# Driver2.net
KiCad netlist of a schematic drawn in Altium Designer
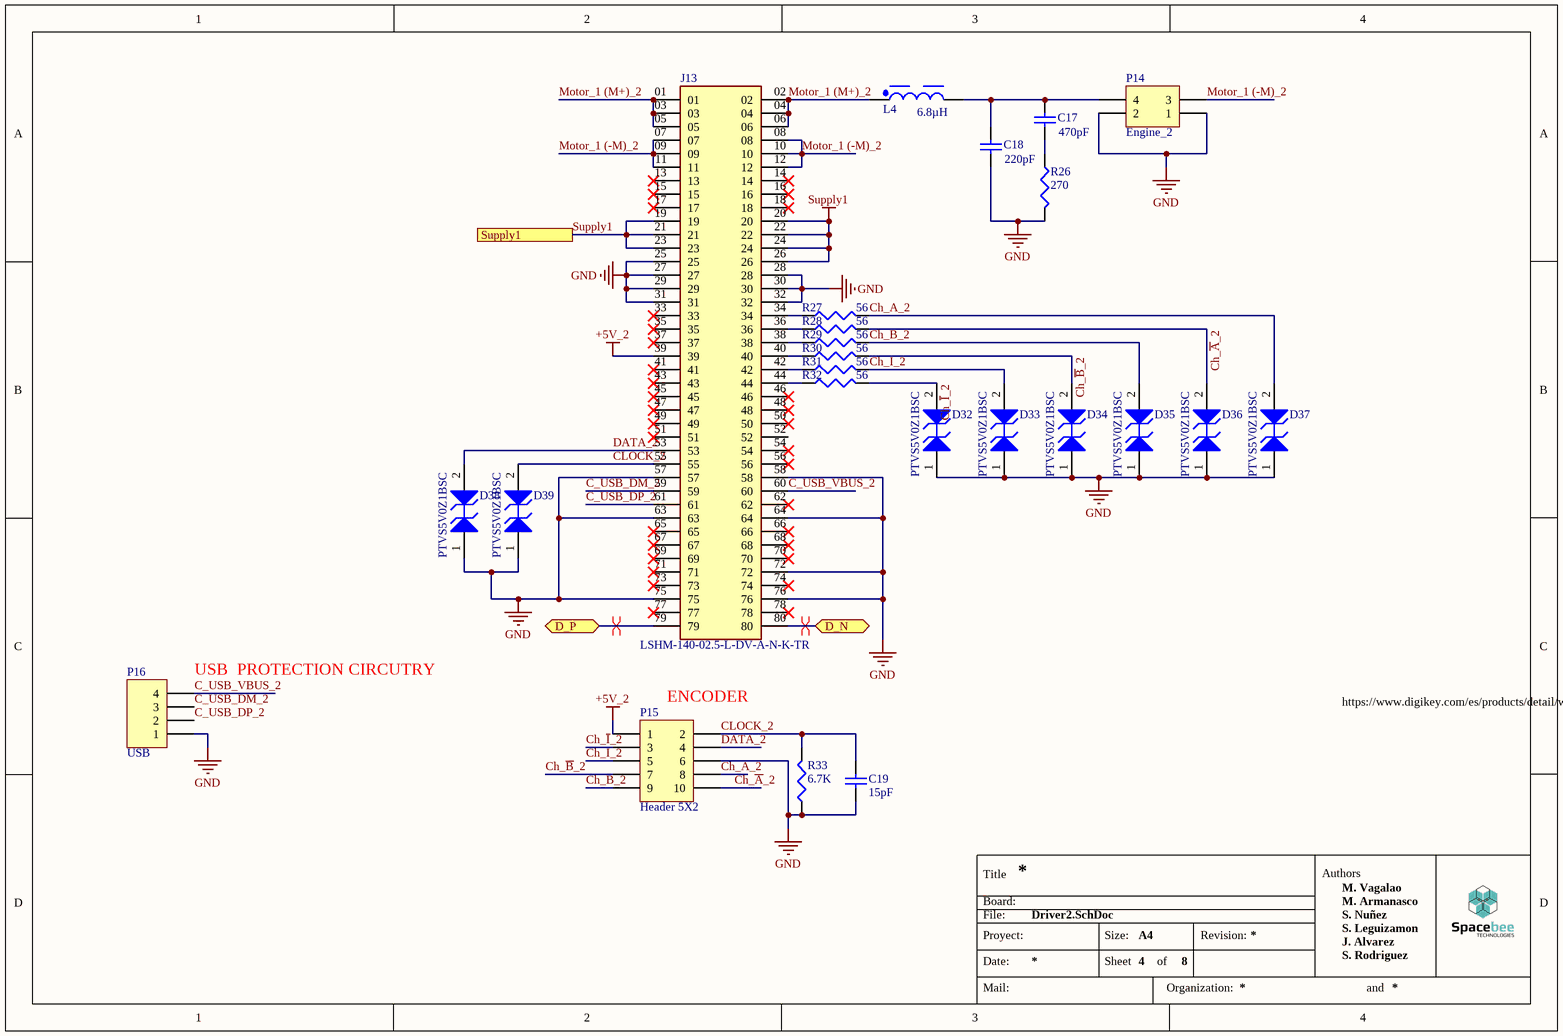
[diagram p0: Driver2.SchDoc]

(export (version "E")
  (design (tool "Eeschema 10.0.6"))
  (components
    (comp (ref "C17")
      (value "470pF")
      (footprint "1608[0603]")
      (description "Capacitor (Semiconductor SIM Model)")
      (fields (field (name "Comment") "Cap Semi") (field (name "PUBLISHER") "Altium Limited"))
      (libsource (lib "Miscellaneous Devices") (part "Cap Semi"))
    )
    (comp (ref "C18")
      (value "220pF")
      (footprint "1608[0603]")
      (description "Capacitor (Semiconductor SIM Model)")
      (fields (field (name "Comment") "Cap Semi") (field (name "PUBLISHER") "Altium Limited"))
      (libsource (lib "Miscellaneous Devices") (part "Cap Semi"))
    )
    (comp (ref "C19")
      (value "15pF")
      (footprint "6-0805_L")
      (description "Capacitor (Semiconductor SIM Model)")
      (fields (field (name "Comment") "Cap Semi") (field (name "PUBLISHER") "Altium Limited"))
      (libsource (lib "SpaceBee") (part "Cap 0805"))
    )
    (comp (ref "D32")
      (value "PTVS5V0Z1BSC")
      (footprint "SOD993B")
      (fields (field (name "MANUFACTURER") "On Semiconductor") (field (name "PARTNUMBER") "1SMB16CAT3"))
      (libsource (lib "DriverLib") (part "PTVS5V0Z1BSC"))
    )
    (comp (ref "D33")
      (value "PTVS5V0Z1BSC")
      (footprint "SOD993B")
      (fields (field (name "MANUFACTURER") "On Semiconductor") (field (name "PARTNUMBER") "1SMB16CAT3"))
      (libsource (lib "DriverLib") (part "PTVS5V0Z1BSC"))
    )
    (comp (ref "D34")
      (value "PTVS5V0Z1BSC")
      (footprint "SOD993B")
      (fields (field (name "MANUFACTURER") "On Semiconductor") (field (name "PARTNUMBER") "1SMB16CAT3"))
      (libsource (lib "DriverLib") (part "PTVS5V0Z1BSC"))
    )
    (comp (ref "D35")
      (value "PTVS5V0Z1BSC")
      (footprint "SOD993B")
      (fields (field (name "MANUFACTURER") "On Semiconductor") (field (name "PARTNUMBER") "1SMB16CAT3"))
      (libsource (lib "DriverLib") (part "PTVS5V0Z1BSC"))
    )
    (comp (ref "D36")
      (value "PTVS5V0Z1BSC")
      (footprint "SOD993B")
      (fields (field (name "MANUFACTURER") "On Semiconductor") (field (name "PARTNUMBER") "1SMB16CAT3"))
      (libsource (lib "DriverLib") (part "PTVS5V0Z1BSC"))
    )
    (comp (ref "D37")
      (value "PTVS5V0Z1BSC")
      (footprint "SOD993B")
      (fields (field (name "MANUFACTURER") "On Semiconductor") (field (name "PARTNUMBER") "1SMB16CAT3"))
      (libsource (lib "DriverLib") (part "PTVS5V0Z1BSC"))
    )
    (comp (ref "D38")
      (value "PTVS5V0Z1BSC")
      (footprint "SOD993B")
      (fields (field (name "MANUFACTURER") "On Semiconductor") (field (name "PARTNUMBER") "1SMB16CAT3"))
      (libsource (lib "DriverLib") (part "PTVS5V0Z1BSC"))
    )
    (comp (ref "D39")
      (value "PTVS5V0Z1BSC")
      (footprint "SOD993B")
      (fields (field (name "MANUFACTURER") "On Semiconductor") (field (name "PARTNUMBER") "1SMB16CAT3"))
      (libsource (lib "DriverLib") (part "PTVS5V0Z1BSC"))
    )
    (comp (ref "J13")
      (value "LSHM-140-02.5-L-DV-A-N-K-TR")
      (footprint "SAMTEC_LSHM-140-02.5-L-DV-A-N-K-TR")
      (description "LSHM - Samtec 0.50mm Razor Beam High-Speed Hermaphroditic Terminal / Socket Strip.")
      (libsource (lib "DriverLib") (part "LSHM-140-02.5-L-DV-A-N-K-TR"))
    )
    (comp (ref "L4")
      (value "6.8µH")
      (footprint "WE-XHMA_6060")
      (description "WE-XHMA SMD Power Inductor, size 1090, 6.8µH, 10.5A, 7.16mΩ")
      (fields
        (field (name "MANUFACTURER PART NUMBER") "78439369068")
        (field (name "MANUFACTURER") "Wurth Elektronik")
      )
      (libsource (lib "DriverLib") (part "78439369068"))
    )
    (comp (ref "P14")
      (value "Engine_2")
      (footprint "MOLEX_1724480004")
      (description "Header, 2-Pin, Dual row")
      (fields (field (name "PUBLISHER") "Altium Limited"))
      (libsource (lib "SpaceBee") (part "Header 2X2"))
    )
    (comp (ref "P15")
      (value "Header 5X2")
      (footprint "CONN_HIF3FC-14PA-2.54DS(71)_HIR")
      (description "Header, 5-Pin, Dual row")
      (fields (field (name "PUBLISHER") "Altium Limited"))
      (libsource (lib "DriverLib") (part "Header 5X2"))
    )
    (comp (ref "P16")
      (value "USB")
      (footprint "Header 4 SMD")
      (description "Header, 4-Pin")
      (fields (field (name "PUBLISHER") "Altium Limited"))
      (libsource (lib "SpaceBee") (part "Header 4 SMD"))
    )
    (comp (ref "R26")
      (value "270")
      (footprint "J1-0603")
      (description "Resistor")
      (fields (field (name "Comment") "Res3") (field (name "PUBLISHER") "Altium Limited"))
      (libsource (lib "Miscellaneous Devices") (part "Res3"))
    )
    (comp (ref "R27")
      (value "56")
      (footprint "J1-0603")
      (description "Resistor")
      (fields (field (name "Comment") "Res3") (field (name "PUBLISHER") "Altium Limited"))
      (libsource (lib "Miscellaneous Devices") (part "Res3"))
    )
    (comp (ref "R28")
      (value "56")
      (footprint "J1-0603")
      (description "Resistor")
      (fields (field (name "Comment") "Res3") (field (name "PUBLISHER") "Altium Limited"))
      (libsource (lib "Miscellaneous Devices") (part "Res3"))
    )
    (comp (ref "R29")
      (value "56")
      (footprint "J1-0603")
      (description "Resistor")
      (fields (field (name "Comment") "Res3") (field (name "PUBLISHER") "Altium Limited"))
      (libsource (lib "Miscellaneous Devices") (part "Res3"))
    )
    (comp (ref "R30")
      (value "56")
      (footprint "J1-0603")
      (description "Resistor")
      (fields (field (name "Comment") "Res3") (field (name "PUBLISHER") "Altium Limited"))
      (libsource (lib "Miscellaneous Devices") (part "Res3"))
    )
    (comp (ref "R31")
      (value "56")
      (footprint "J1-0603")
      (description "Resistor")
      (fields (field (name "Comment") "Res3") (field (name "PUBLISHER") "Altium Limited"))
      (libsource (lib "Miscellaneous Devices") (part "Res3"))
    )
    (comp (ref "R32")
      (value "56")
      (footprint "J1-0603")
      (description "Resistor")
      (fields (field (name "Comment") "Res3") (field (name "PUBLISHER") "Altium Limited"))
      (libsource (lib "Miscellaneous Devices") (part "Res3"))
    )
    (comp (ref "R33")
      (value "6.7K")
      (footprint "J1-0603")
      (description "Resistor")
      (fields (field (name "Comment") "Res3") (field (name "PUBLISHER") "Altium Limited"))
      (libsource (lib "Miscellaneous Devices") (part "Res3"))
    )
  )
  (nets
    (net (code "1") (name "+5V_2") (class "Default")
      (node (ref "J13") (pin "39") (pinfunction "39_39") (pintype "passive"))
      (node (ref "P15") (pin "1") (pinfunction "1_1") (pintype "passive"))
    )
    (net (code "2") (name "/CLOCK_2") (class "Default")
      (node (ref "C19") (pin "2") (pinfunction "2_2") (pintype "passive"))
      (node (ref "D39") (pin "2") (pinfunction "A2_2") (pintype "passive"))
      (node (ref "J13") (pin "55") (pinfunction "55_55") (pintype "passive"))
      (node (ref "P15") (pin "2") (pinfunction "2_2") (pintype "passive"))
      (node (ref "R33") (pin "2") (pinfunction "2_2") (pintype "passive"))
    )
    (net (code "3") (name "/C_USB_DM_2") (class "Default")
      (node (ref "J13") (pin "59") (pinfunction "59_59") (pintype "passive"))
      (node (ref "P16") (pin "3") (pinfunction "3_3") (pintype "passive"))
    )
    (net (code "4") (name "/C_USB_DP_2") (class "Default")
      (node (ref "J13") (pin "61") (pinfunction "61_61") (pintype "passive"))
      (node (ref "P16") (pin "2") (pinfunction "2_2") (pintype "passive"))
    )
    (net (code "5") (name "/C_USB_VBUS_2") (class "Default")
      (node (ref "J13") (pin "60") (pinfunction "60_60") (pintype "passive"))
      (node (ref "P16") (pin "4") (pinfunction "4_4") (pintype "passive"))
    )
    (net (code "6") (name "/Ch_A_2") (class "Default")
      (node (ref "D37") (pin "2") (pinfunction "A2_2") (pintype "passive"))
      (node (ref "P15") (pin "8") (pinfunction "8_8") (pintype "passive"))
      (node (ref "R27") (pin "2") (pinfunction "2_2") (pintype "passive"))
    )
    (net (code "7") (name "/Ch_B_2") (class "Default")
      (node (ref "D35") (pin "2") (pinfunction "A2_2") (pintype "passive"))
      (node (ref "P15") (pin "9") (pinfunction "9_9") (pintype "passive"))
      (node (ref "R29") (pin "2") (pinfunction "2_2") (pintype "passive"))
    )
    (net (code "8") (name "/Ch_I_2") (class "Default")
      (node (ref "D33") (pin "2") (pinfunction "A2_2") (pintype "passive"))
      (node (ref "P15") (pin "5") (pinfunction "5_5") (pintype "passive"))
      (node (ref "R31") (pin "2") (pinfunction "2_2") (pintype "passive"))
    )
    (net (code "9") (name "/Ch_~{A}_2") (class "Default")
      (node (ref "D36") (pin "2") (pinfunction "A2_2") (pintype "passive"))
      (node (ref "P15") (pin "10") (pinfunction "10_10") (pintype "passive"))
      (node (ref "R28") (pin "2") (pinfunction "2_2") (pintype "passive"))
    )
    (net (code "10") (name "/Ch_~{B}_2") (class "Default")
      (node (ref "D34") (pin "2") (pinfunction "A2_2") (pintype "passive"))
      (node (ref "P15") (pin "7") (pinfunction "7_7") (pintype "passive"))
      (node (ref "R30") (pin "2") (pinfunction "2_2") (pintype "passive"))
    )
    (net (code "11") (name "/Ch_~{I}_2") (class "Default")
      (node (ref "D32") (pin "2") (pinfunction "A2_2") (pintype "passive"))
      (node (ref "P15") (pin "3") (pinfunction "3_3") (pintype "passive"))
      (node (ref "R32") (pin "2") (pinfunction "2_2") (pintype "passive"))
    )
    (net (code "12") (name "/DATA_2") (class "Default")
      (node (ref "D38") (pin "2") (pinfunction "A2_2") (pintype "passive"))
      (node (ref "J13") (pin "53") (pinfunction "53_53") (pintype "passive"))
      (node (ref "P15") (pin "4") (pinfunction "4_4") (pintype "passive"))
    )
    (net (code "13") (name "/D_N") (class "Default")
      (node (ref "J13") (pin "80") (pinfunction "80_80") (pintype "passive"))
    )
    (net (code "14") (name "/D_P") (class "Default")
      (node (ref "J13") (pin "79") (pinfunction "79_79") (pintype "passive"))
    )
    (net (code "15") (name "/Motor_1 (-M)_2") (class "Default")
      (node (ref "J13") (pin "07") (pinfunction "07_07") (pintype "passive"))
      (node (ref "J13") (pin "08") (pinfunction "08_08") (pintype "passive"))
      (node (ref "J13") (pin "09") (pinfunction "09_09") (pintype "passive"))
      (node (ref "J13") (pin "10") (pinfunction "10_10") (pintype "passive"))
      (node (ref "J13") (pin "11") (pinfunction "11_11") (pintype "passive"))
      (node (ref "J13") (pin "12") (pinfunction "12_12") (pintype "passive"))
      (node (ref "P14") (pin "3") (pinfunction "3_3") (pintype "passive"))
    )
    (net (code "16") (name "/Motor_1 (M+)_2") (class "Default")
      (node (ref "J13") (pin "01") (pinfunction "01_01") (pintype "passive"))
      (node (ref "J13") (pin "02") (pinfunction "02_02") (pintype "passive"))
      (node (ref "J13") (pin "03") (pinfunction "03_03") (pintype "passive"))
      (node (ref "J13") (pin "04") (pinfunction "04_04") (pintype "passive"))
      (node (ref "J13") (pin "05") (pinfunction "05_05") (pintype "passive"))
      (node (ref "J13") (pin "06") (pinfunction "06_06") (pintype "passive"))
      (node (ref "L4") (pin "1") (pinfunction "1_1") (pintype "passive"))
    )
    (net (code "17") (name "GND") (class "Default")
      (node (ref "C18") (pin "2") (pinfunction "2_2") (pintype "passive"))
      (node (ref "C19") (pin "1") (pinfunction "1_1") (pintype "passive"))
      (node (ref "D32") (pin "1") (pinfunction "A1_1") (pintype "passive"))
      (node (ref "D33") (pin "1") (pinfunction "A1_1") (pintype "passive"))
      (node (ref "D34") (pin "1") (pinfunction "A1_1") (pintype "passive"))
      (node (ref "D35") (pin "1") (pinfunction "A1_1") (pintype "passive"))
      (node (ref "D36") (pin "1") (pinfunction "A1_1") (pintype "passive"))
      (node (ref "D37") (pin "1") (pinfunction "A1_1") (pintype "passive"))
      (node (ref "D38") (pin "1") (pinfunction "A1_1") (pintype "passive"))
      (node (ref "D39") (pin "1") (pinfunction "A1_1") (pintype "passive"))
      (node (ref "J13") (pin "25") (pinfunction "25_25") (pintype "passive"))
      (node (ref "J13") (pin "27") (pinfunction "27_27") (pintype "passive"))
      (node (ref "J13") (pin "28") (pinfunction "28_28") (pintype "passive"))
      (node (ref "J13") (pin "29") (pinfunction "29_29") (pintype "passive"))
      (node (ref "J13") (pin "30") (pinfunction "30_30") (pintype "passive"))
      (node (ref "J13") (pin "31") (pinfunction "31_31") (pintype "passive"))
      (node (ref "J13") (pin "32") (pinfunction "32_32") (pintype "passive"))
      (node (ref "J13") (pin "57") (pinfunction "57_57") (pintype "passive"))
      (node (ref "J13") (pin "58") (pinfunction "58_58") (pintype "passive"))
      (node (ref "J13") (pin "63") (pinfunction "63_63") (pintype "passive"))
      (node (ref "J13") (pin "64") (pinfunction "64_64") (pintype "passive"))
      (node (ref "J13") (pin "72") (pinfunction "72_72") (pintype "passive"))
      (node (ref "J13") (pin "75") (pinfunction "75_75") (pintype "passive"))
      (node (ref "J13") (pin "76") (pinfunction "76_76") (pintype "passive"))
      (node (ref "P14") (pin "1") (pinfunction "1_1") (pintype "passive"))
      (node (ref "P14") (pin "2") (pinfunction "2_2") (pintype "passive"))
      (node (ref "P15") (pin "6") (pinfunction "6_6") (pintype "passive"))
      (node (ref "P16") (pin "1") (pinfunction "1_1") (pintype "passive"))
      (node (ref "R26") (pin "2") (pinfunction "2_2") (pintype "passive"))
      (node (ref "R33") (pin "1") (pinfunction "1_1") (pintype "passive"))
    )
    (net (code "18") (name "Net-(C17-Pad1)") (class "Default")
      (node (ref "C17") (pin "1") (pinfunction "1_1") (pintype "passive"))
      (node (ref "C18") (pin "1") (pinfunction "1_1") (pintype "passive"))
      (node (ref "L4") (pin "2") (pinfunction "2_2") (pintype "passive"))
      (node (ref "P14") (pin "4") (pinfunction "4_4") (pintype "passive"))
    )
    (net (code "19") (name "Net-(C17-Pad2)") (class "Default")
      (node (ref "C17") (pin "2") (pinfunction "2_2") (pintype "passive"))
      (node (ref "R26") (pin "1") (pinfunction "1_1") (pintype "passive"))
    )
    (net (code "20") (name "Net-(J13-Pad34)") (class "Default")
      (node (ref "J13") (pin "34") (pinfunction "34_34") (pintype "passive"))
      (node (ref "R27") (pin "1") (pinfunction "1_1") (pintype "passive"))
    )
    (net (code "21") (name "Net-(J13-Pad36)") (class "Default")
      (node (ref "J13") (pin "36") (pinfunction "36_36") (pintype "passive"))
      (node (ref "R28") (pin "1") (pinfunction "1_1") (pintype "passive"))
    )
    (net (code "22") (name "Net-(J13-Pad38)") (class "Default")
      (node (ref "J13") (pin "38") (pinfunction "38_38") (pintype "passive"))
      (node (ref "R29") (pin "1") (pinfunction "1_1") (pintype "passive"))
    )
    (net (code "23") (name "Net-(J13-Pad40)") (class "Default")
      (node (ref "J13") (pin "40") (pinfunction "40_40") (pintype "passive"))
      (node (ref "R30") (pin "1") (pinfunction "1_1") (pintype "passive"))
    )
    (net (code "24") (name "Net-(J13-Pad42)") (class "Default")
      (node (ref "J13") (pin "42") (pinfunction "42_42") (pintype "passive"))
      (node (ref "R31") (pin "1") (pinfunction "1_1") (pintype "passive"))
    )
    (net (code "25") (name "Net-(J13-Pad44)") (class "Default")
      (node (ref "J13") (pin "44") (pinfunction "44_44") (pintype "passive"))
      (node (ref "R32") (pin "1") (pinfunction "1_1") (pintype "passive"))
    )
    (net (code "26") (name "Supply1") (class "Default")
      (node (ref "J13") (pin "19") (pinfunction "19_19") (pintype "passive"))
      (node (ref "J13") (pin "20") (pinfunction "20_20") (pintype "passive"))
      (node (ref "J13") (pin "21") (pinfunction "21_21") (pintype "passive"))
      (node (ref "J13") (pin "22") (pinfunction "22_22") (pintype "passive"))
      (node (ref "J13") (pin "23") (pinfunction "23_23") (pintype "passive"))
      (node (ref "J13") (pin "24") (pinfunction "24_24") (pintype "passive"))
      (node (ref "J13") (pin "26") (pinfunction "26_26") (pintype "passive"))
    )
    (net (code "27") (name "unconnected-(J13-Pad13)") (class "Default")
      (node (ref "J13") (pin "13") (pinfunction "13_13") (pintype "passive+no_connect"))
    )
    (net (code "28") (name "unconnected-(J13-Pad14)") (class "Default")
      (node (ref "J13") (pin "14") (pinfunction "14_14") (pintype "passive+no_connect"))
    )
    (net (code "29") (name "unconnected-(J13-Pad15)") (class "Default")
      (node (ref "J13") (pin "15") (pinfunction "15_15") (pintype "passive+no_connect"))
    )
    (net (code "30") (name "unconnected-(J13-Pad16)") (class "Default")
      (node (ref "J13") (pin "16") (pinfunction "16_16") (pintype "passive+no_connect"))
    )
    (net (code "31") (name "unconnected-(J13-Pad17)") (class "Default")
      (node (ref "J13") (pin "17") (pinfunction "17_17") (pintype "passive+no_connect"))
    )
    (net (code "32") (name "unconnected-(J13-Pad18)") (class "Default")
      (node (ref "J13") (pin "18") (pinfunction "18_18") (pintype "passive+no_connect"))
    )
    (net (code "33") (name "unconnected-(J13-Pad33)") (class "Default")
      (node (ref "J13") (pin "33") (pinfunction "33_33") (pintype "passive+no_connect"))
    )
    (net (code "34") (name "unconnected-(J13-Pad35)") (class "Default")
      (node (ref "J13") (pin "35") (pinfunction "35_35") (pintype "passive+no_connect"))
    )
    (net (code "35") (name "unconnected-(J13-Pad37)") (class "Default")
      (node (ref "J13") (pin "37") (pinfunction "37_37") (pintype "passive+no_connect"))
    )
    (net (code "36") (name "unconnected-(J13-Pad41)") (class "Default")
      (node (ref "J13") (pin "41") (pinfunction "41_41") (pintype "passive+no_connect"))
    )
    (net (code "37") (name "unconnected-(J13-Pad43)") (class "Default")
      (node (ref "J13") (pin "43") (pinfunction "43_43") (pintype "passive+no_connect"))
    )
    (net (code "38") (name "unconnected-(J13-Pad45)") (class "Default")
      (node (ref "J13") (pin "45") (pinfunction "45_45") (pintype "passive+no_connect"))
    )
    (net (code "39") (name "unconnected-(J13-Pad46)") (class "Default")
      (node (ref "J13") (pin "46") (pinfunction "46_46") (pintype "passive+no_connect"))
    )
    (net (code "40") (name "unconnected-(J13-Pad47)") (class "Default")
      (node (ref "J13") (pin "47") (pinfunction "47_47") (pintype "passive+no_connect"))
    )
    (net (code "41") (name "unconnected-(J13-Pad48)") (class "Default")
      (node (ref "J13") (pin "48") (pinfunction "48_48") (pintype "passive+no_connect"))
    )
    (net (code "42") (name "unconnected-(J13-Pad49)") (class "Default")
      (node (ref "J13") (pin "49") (pinfunction "49_49") (pintype "passive+no_connect"))
    )
    (net (code "43") (name "unconnected-(J13-Pad50)") (class "Default")
      (node (ref "J13") (pin "50") (pinfunction "50_50") (pintype "passive+no_connect"))
    )
    (net (code "44") (name "unconnected-(J13-Pad51)") (class "Default")
      (node (ref "J13") (pin "51") (pinfunction "51_51") (pintype "passive+no_connect"))
    )
    (net (code "45") (name "unconnected-(J13-Pad52)") (class "Default")
      (node (ref "J13") (pin "52") (pinfunction "52_52") (pintype "passive"))
    )
    (net (code "46") (name "unconnected-(J13-Pad54)") (class "Default")
      (node (ref "J13") (pin "54") (pinfunction "54_54") (pintype "passive+no_connect"))
    )
    (net (code "47") (name "unconnected-(J13-Pad56)") (class "Default")
      (node (ref "J13") (pin "56") (pinfunction "56_56") (pintype "passive+no_connect"))
    )
    (net (code "48") (name "unconnected-(J13-Pad62)") (class "Default")
      (node (ref "J13") (pin "62") (pinfunction "62_62") (pintype "passive+no_connect"))
    )
    (net (code "49") (name "unconnected-(J13-Pad65)") (class "Default")
      (node (ref "J13") (pin "65") (pinfunction "65_65") (pintype "passive+no_connect"))
    )
    (net (code "50") (name "unconnected-(J13-Pad66)") (class "Default")
      (node (ref "J13") (pin "66") (pinfunction "66_66") (pintype "passive+no_connect"))
    )
    (net (code "51") (name "unconnected-(J13-Pad67)") (class "Default")
      (node (ref "J13") (pin "67") (pinfunction "67_67") (pintype "passive+no_connect"))
    )
    (net (code "52") (name "unconnected-(J13-Pad68)") (class "Default")
      (node (ref "J13") (pin "68") (pinfunction "68_68") (pintype "passive+no_connect"))
    )
    (net (code "53") (name "unconnected-(J13-Pad69)") (class "Default")
      (node (ref "J13") (pin "69") (pinfunction "69_69") (pintype "passive+no_connect"))
    )
    (net (code "54") (name "unconnected-(J13-Pad70)") (class "Default")
      (node (ref "J13") (pin "70") (pinfunction "70_70") (pintype "passive+no_connect"))
    )
    (net (code "55") (name "unconnected-(J13-Pad71)") (class "Default")
      (node (ref "J13") (pin "71") (pinfunction "71_71") (pintype "passive+no_connect"))
    )
    (net (code "56") (name "unconnected-(J13-Pad73)") (class "Default")
      (node (ref "J13") (pin "73") (pinfunction "73_73") (pintype "passive+no_connect"))
    )
    (net (code "57") (name "unconnected-(J13-Pad74)") (class "Default")
      (node (ref "J13") (pin "74") (pinfunction "74_74") (pintype "passive+no_connect"))
    )
    (net (code "58") (name "unconnected-(J13-Pad77)") (class "Default")
      (node (ref "J13") (pin "77") (pinfunction "77_77") (pintype "passive+no_connect"))
    )
    (net (code "59") (name "unconnected-(J13-Pad78)") (class "Default")
      (node (ref "J13") (pin "78") (pinfunction "78_78") (pintype "passive+no_connect"))
    )
  )
)
